# working.net
KiCad netlist of a schematic drawn in EAGLE
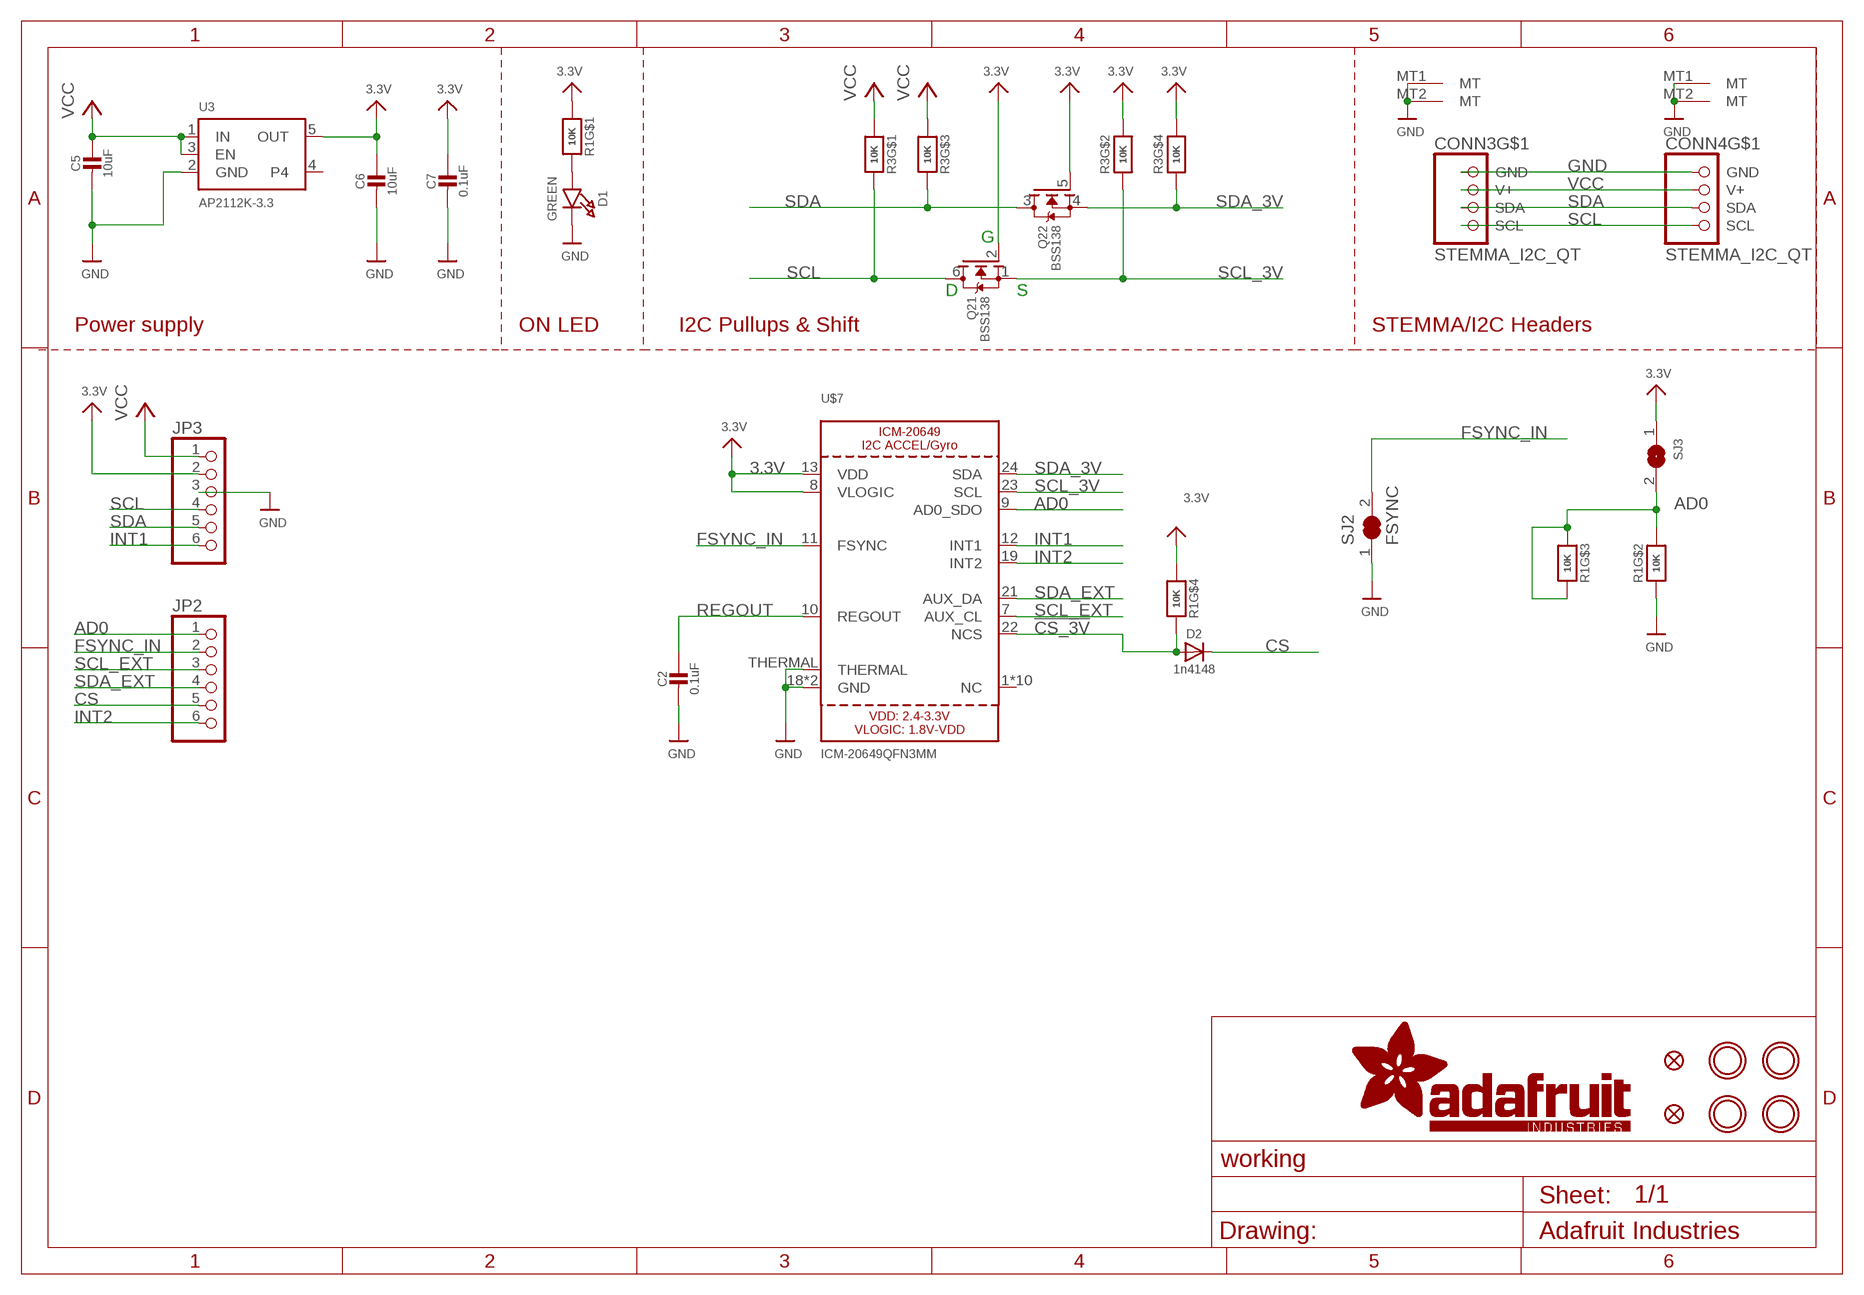
[diagram p0: schematic, sheet 1]

(export (version "E")
  (design (tool "Eeschema 10.0.6"))
  (components
    (comp (ref "C2")
      (value "0.1uF")
      (footprint "eagle-import:0603-NO")
      (libsource (lib "eagle-import") (part "CAP_CERAMIC0603_NO"))
    )
    (comp (ref "C5")
      (value "10uF")
      (footprint "eagle-import:0805-NO")
      (libsource (lib "eagle-import") (part "CAP_CERAMIC0805-NOOUTLINE"))
    )
    (comp (ref "C6")
      (value "10uF")
      (footprint "eagle-import:0805-NO")
      (libsource (lib "eagle-import") (part "CAP_CERAMIC0805-NOOUTLINE"))
    )
    (comp (ref "C7")
      (value "0.1uF")
      (footprint "eagle-import:0603-NO")
      (libsource (lib "eagle-import") (part "CAP_CERAMIC0603_NO"))
    )
    (comp (ref "CONN3")
      (value "STEMMA_I2C_QT")
      (footprint "eagle-import:JST_SH4")
      (libsource (lib "eagle-import") (part "STEMMA_I2C_QT"))
    )
    (comp (ref "CONN4")
      (value "STEMMA_I2C_QT")
      (footprint "eagle-import:JST_SH4")
      (libsource (lib "eagle-import") (part "STEMMA_I2C_QT"))
    )
    (comp (ref "D1")
      (value "GREEN")
      (footprint "eagle-import:CHIPLED_0603_NOOUTLINE")
      (libsource (lib "eagle-import") (part "LED0603_NOOUTLINE"))
    )
    (comp (ref "D2")
      (value "1n4148")
      (footprint "eagle-import:SOD-323")
      (libsource (lib "eagle-import") (part "DIODESOD-323"))
    )
    (comp (ref "FID3")
      (value "FIDUCIAL_1MM")
      (footprint "eagle-import:FIDUCIAL_1MM")
      (libsource (lib "eagle-import") (part "FIDUCIAL_1MM"))
    )
    (comp (ref "FID4")
      (value "FIDUCIAL_1MM")
      (footprint "eagle-import:FIDUCIAL_1MM")
      (libsource (lib "eagle-import") (part "FIDUCIAL_1MM"))
    )
    (comp (ref "JP2")
      (value "HEADER-1X6ROUND")
      (footprint "eagle-import:1X06_ROUND")
      (libsource (lib "eagle-import") (part "HEADER-1X6ROUND"))
    )
    (comp (ref "JP3")
      (value "HEADER-1X670MIL")
      (footprint "eagle-import:1X06_ROUND_70")
      (libsource (lib "eagle-import") (part "HEADER-1X670MIL"))
    )
    (comp (ref "Q2")
      (value "BSS138")
      (footprint "eagle-import:SOT363")
      (libsource (lib "eagle-import") (part "MOSFET-N_DUAL"))
    )
    (comp (ref "R1")
      (value "10K")
      (footprint "eagle-import:RESPACK_4X0603")
      (libsource (lib "eagle-import") (part "RESISTOR_4PACK"))
    )
    (comp (ref "R3")
      (value "10K")
      (footprint "eagle-import:RESPACK_4X0603")
      (libsource (lib "eagle-import") (part "RESISTOR_4PACK"))
    )
    (comp (ref "SJ2")
      (value "FSYNC")
      (footprint "eagle-import:SOLDERJUMPER_CLOSEDWIRE")
      (libsource (lib "eagle-import") (part "SOLDERJUMPER_CLOSED"))
    )
    (comp (ref "SJ3")
      (value "SOLDERJUMPER")
      (footprint "eagle-import:SOLDERJUMPER_ARROW_NOPASTE")
      (libsource (lib "eagle-import") (part "SOLDERJUMPER"))
    )
    (comp (ref "U$7")
      (value "ICM-20649QFN3MM")
      (footprint "eagle-import:QFN24_3MM")
      (libsource (lib "eagle-import") (part "ICM-20649QFN3MM"))
    )
    (comp (ref "U$39")
      (value "MOUNTINGHOLE2.5")
      (footprint "eagle-import:MOUNTINGHOLE_2.5_PLATED")
      (libsource (lib "eagle-import") (part "MOUNTINGHOLE2.5"))
    )
    (comp (ref "U$40")
      (value "MOUNTINGHOLE2.5")
      (footprint "eagle-import:MOUNTINGHOLE_2.5_PLATED")
      (libsource (lib "eagle-import") (part "MOUNTINGHOLE2.5"))
    )
    (comp (ref "U$42")
      (value "MOUNTINGHOLE2.5")
      (footprint "eagle-import:MOUNTINGHOLE_2.5_PLATED")
      (libsource (lib "eagle-import") (part "MOUNTINGHOLE2.5"))
    )
    (comp (ref "U$43")
      (value "MOUNTINGHOLE2.5")
      (footprint "eagle-import:MOUNTINGHOLE_2.5_PLATED")
      (libsource (lib "eagle-import") (part "MOUNTINGHOLE2.5"))
    )
    (comp (ref "U3")
      (value "AP2112K-3.3")
      (footprint "eagle-import:SOT23-5")
      (libsource (lib "eagle-import") (part "VREG_SOT23-5"))
    )
  )
  (nets
    (net (code "1") (name "/AD0") (class "Default")
      (node (ref "JP2") (pin "1") (pinfunction "1_1") (pintype "passive"))
      (node (ref "R1") (pin "3") (pinfunction "1_3") (pintype "passive"))
      (node (ref "R1") (pin "6") (pinfunction "2_6") (pintype "passive"))
      (node (ref "R1") (pin "7") (pinfunction "2_7") (pintype "passive"))
      (node (ref "SJ3") (pin "2") (pinfunction "2_2") (pintype "passive"))
      (node (ref "U$7") (pin "9") (pinfunction "AD0_SDO_9") (pintype "input"))
    )
    (net (code "2") (name "/CS") (class "Default")
      (node (ref "D2") (pin "C") (pinfunction "C_C") (pintype "passive"))
      (node (ref "JP2") (pin "5") (pinfunction "5_5") (pintype "passive"))
    )
    (net (code "3") (name "/FSYNC_IN") (class "Default")
      (node (ref "JP2") (pin "2") (pinfunction "2_2") (pintype "passive"))
      (node (ref "SJ2") (pin "2") (pinfunction "2_2") (pintype "passive"))
      (node (ref "U$7") (pin "11") (pinfunction "FSYNC_11") (pintype "input"))
    )
    (net (code "4") (name "/INT1") (class "Default")
      (node (ref "JP3") (pin "6") (pinfunction "6_6") (pintype "passive"))
      (node (ref "U$7") (pin "12") (pinfunction "INT1_12") (pintype "output"))
    )
    (net (code "5") (name "/INT2") (class "Default")
      (node (ref "JP2") (pin "6") (pinfunction "6_6") (pintype "passive"))
      (node (ref "U$7") (pin "19") (pinfunction "INT2_19") (pintype "output"))
    )
    (net (code "6") (name "/REGOUT") (class "Default")
      (node (ref "C2") (pin "1") (pinfunction "1_1") (pintype "passive"))
      (node (ref "U$7") (pin "10") (pinfunction "REGOUT_10") (pintype "passive"))
    )
    (net (code "7") (name "/SCL") (class "Default")
      (node (ref "CONN3") (pin "4") (pinfunction "SCL_4") (pintype "passive"))
      (node (ref "CONN4") (pin "4") (pinfunction "SCL_4") (pintype "passive"))
      (node (ref "JP3") (pin "4") (pinfunction "4_4") (pintype "passive"))
      (node (ref "Q2") (pin "6") (pinfunction "D_6") (pintype "bidirectional"))
      (node (ref "R3") (pin "8") (pinfunction "2_8") (pintype "passive"))
    )
    (net (code "8") (name "/SCL_3V") (class "Default")
      (node (ref "Q2") (pin "1") (pinfunction "S_1") (pintype "bidirectional"))
      (node (ref "R3") (pin "7") (pinfunction "2_7") (pintype "passive"))
      (node (ref "U$7") (pin "23") (pinfunction "SCL_23") (pintype "bidirectional"))
    )
    (net (code "9") (name "/SCL_EXT") (class "Default")
      (node (ref "JP2") (pin "3") (pinfunction "3_3") (pintype "passive"))
      (node (ref "U$7") (pin "7") (pinfunction "AUX_CL_7") (pintype "bidirectional"))
    )
    (net (code "10") (name "/SDA") (class "Default")
      (node (ref "CONN3") (pin "3") (pinfunction "SDA_3") (pintype "passive"))
      (node (ref "CONN4") (pin "3") (pinfunction "SDA_3") (pintype "passive"))
      (node (ref "JP3") (pin "5") (pinfunction "5_5") (pintype "passive"))
      (node (ref "Q2") (pin "3") (pinfunction "D_3") (pintype "bidirectional"))
      (node (ref "R3") (pin "6") (pinfunction "2_6") (pintype "passive"))
    )
    (net (code "11") (name "/SDA_3V") (class "Default")
      (node (ref "Q2") (pin "4") (pinfunction "S_4") (pintype "bidirectional"))
      (node (ref "R3") (pin "5") (pinfunction "2_5") (pintype "passive"))
      (node (ref "U$7") (pin "24") (pinfunction "SDA_24") (pintype "bidirectional"))
    )
    (net (code "12") (name "/SDA_EXT") (class "Default")
      (node (ref "JP2") (pin "4") (pinfunction "4_4") (pintype "passive"))
      (node (ref "U$7") (pin "21") (pinfunction "AUX_DA_21") (pintype "bidirectional"))
    )
    (net (code "13") (name "/~{CS_3V}") (class "Default")
      (node (ref "D2") (pin "A") (pinfunction "A_A") (pintype "passive"))
      (node (ref "R1") (pin "5") (pinfunction "2_5") (pintype "passive"))
      (node (ref "U$7") (pin "22") (pinfunction "NCS_22") (pintype "input"))
    )
    (net (code "14") (name "3.3V") (class "Default")
      (node (ref "C6") (pin "1") (pinfunction "1_1") (pintype "passive"))
      (node (ref "C7") (pin "1") (pinfunction "1_1") (pintype "passive"))
      (node (ref "JP3") (pin "2") (pinfunction "2_2") (pintype "passive"))
      (node (ref "Q2") (pin "2") (pinfunction "G_2") (pintype "bidirectional"))
      (node (ref "Q2") (pin "5") (pinfunction "G_5") (pintype "bidirectional"))
      (node (ref "R1") (pin "1") (pinfunction "1_1") (pintype "passive"))
      (node (ref "R1") (pin "4") (pinfunction "1_4") (pintype "passive"))
      (node (ref "R3") (pin "2") (pinfunction "1_2") (pintype "passive"))
      (node (ref "R3") (pin "4") (pinfunction "1_4") (pintype "passive"))
      (node (ref "SJ3") (pin "1") (pinfunction "1_1") (pintype "passive"))
      (node (ref "U$7") (pin "13") (pinfunction "VDD_13") (pintype "power_in"))
      (node (ref "U$7") (pin "8") (pinfunction "VLOGIC_8") (pintype "power_in"))
      (node (ref "U3") (pin "5") (pinfunction "OUT_5") (pintype "power_in"))
    )
    (net (code "15") (name "GND") (class "Default")
      (node (ref "C2") (pin "2") (pinfunction "2_2") (pintype "passive"))
      (node (ref "C5") (pin "2") (pinfunction "2_2") (pintype "passive"))
      (node (ref "C6") (pin "2") (pinfunction "2_2") (pintype "passive"))
      (node (ref "C7") (pin "2") (pinfunction "2_2") (pintype "passive"))
      (node (ref "CONN3") (pin "1") (pinfunction "GND_1") (pintype "passive"))
      (node (ref "CONN3") (pin "MT1") (pinfunction "MT_MT1") (pintype "bidirectional"))
      (node (ref "CONN3") (pin "MT2") (pinfunction "MT_MT2") (pintype "bidirectional"))
      (node (ref "CONN4") (pin "1") (pinfunction "GND_1") (pintype "passive"))
      (node (ref "CONN4") (pin "MT1") (pinfunction "MT_MT1") (pintype "bidirectional"))
      (node (ref "CONN4") (pin "MT2") (pinfunction "MT_MT2") (pintype "bidirectional"))
      (node (ref "D1") (pin "C") (pinfunction "C_C") (pintype "passive"))
      (node (ref "JP3") (pin "3") (pinfunction "3_3") (pintype "passive"))
      (node (ref "R1") (pin "2") (pinfunction "1_2") (pintype "passive"))
      (node (ref "SJ2") (pin "1") (pinfunction "1_1") (pintype "passive"))
      (node (ref "U$7") (pin "18") (pinfunction "GND_18") (pintype "power_in"))
      (node (ref "U$7") (pin "20") (pinfunction "GND_20") (pintype "power_in"))
      (node (ref "U$7") (pin "THERMAL") (pinfunction "THERMAL_THERMAL") (pintype "power_in"))
      (node (ref "U3") (pin "2") (pinfunction "GND_2") (pintype "power_in"))
    )
    (net (code "16") (name "Net-(R1A-2)") (class "Default")
      (node (ref "D1") (pin "A") (pinfunction "A_A") (pintype "passive"))
      (node (ref "R1") (pin "8") (pinfunction "2_8") (pintype "passive"))
    )
    (net (code "17") (name "VCC") (class "Default")
      (node (ref "C5") (pin "1") (pinfunction "1_1") (pintype "passive"))
      (node (ref "CONN3") (pin "2") (pinfunction "V+_2") (pintype "passive"))
      (node (ref "CONN4") (pin "2") (pinfunction "V+_2") (pintype "passive"))
      (node (ref "JP3") (pin "1") (pinfunction "1_1") (pintype "passive"))
      (node (ref "R3") (pin "1") (pinfunction "1_1") (pintype "passive"))
      (node (ref "R3") (pin "3") (pinfunction "1_3") (pintype "passive"))
      (node (ref "U3") (pin "1") (pinfunction "IN_1") (pintype "power_in"))
      (node (ref "U3") (pin "3") (pinfunction "EN_3") (pintype "input"))
    )
    (net (code "18") (name "unconnected-(U$7-NC-Pad1)") (class "Default")
      (node (ref "U$7") (pin "1") (pinfunction "NC_1") (pintype "no_connect"))
    )
    (net (code "19") (name "unconnected-(U$7-NC-Pad2)") (class "Default")
      (node (ref "U$7") (pin "2") (pinfunction "NC_2") (pintype "no_connect"))
    )
    (net (code "20") (name "unconnected-(U$7-NC-Pad3)") (class "Default")
      (node (ref "U$7") (pin "3") (pinfunction "NC_3") (pintype "no_connect"))
    )
    (net (code "21") (name "unconnected-(U$7-NC-Pad4)") (class "Default")
      (node (ref "U$7") (pin "4") (pinfunction "NC_4") (pintype "no_connect"))
    )
    (net (code "22") (name "unconnected-(U$7-NC-Pad5)") (class "Default")
      (node (ref "U$7") (pin "5") (pinfunction "NC_5") (pintype "no_connect"))
    )
    (net (code "23") (name "unconnected-(U$7-NC-Pad6)") (class "Default")
      (node (ref "U$7") (pin "6") (pinfunction "NC_6") (pintype "no_connect"))
    )
    (net (code "24") (name "unconnected-(U$7-NC-Pad14)") (class "Default")
      (node (ref "U$7") (pin "14") (pinfunction "NC_14") (pintype "no_connect"))
    )
    (net (code "25") (name "unconnected-(U$7-NC-Pad15)") (class "Default")
      (node (ref "U$7") (pin "15") (pinfunction "NC_15") (pintype "no_connect"))
    )
    (net (code "26") (name "unconnected-(U$7-NC-Pad16)") (class "Default")
      (node (ref "U$7") (pin "16") (pinfunction "NC_16") (pintype "no_connect"))
    )
    (net (code "27") (name "unconnected-(U$7-NC-Pad17)") (class "Default")
      (node (ref "U$7") (pin "17") (pinfunction "NC_17") (pintype "no_connect"))
    )
    (net (code "28") (name "unconnected-(U3-P4-Pad4)") (class "Default")
      (node (ref "U3") (pin "4") (pinfunction "P4_4") (pintype "bidirectional"))
    )
  )
)
